# Keyboard.net
KiCad netlist of a schematic drawn in EAGLE
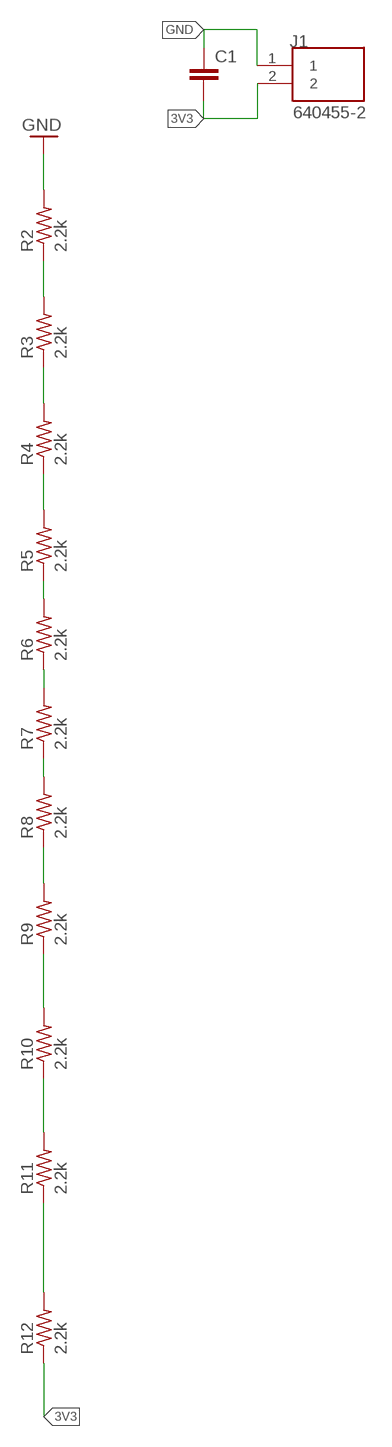
[diagram p0: schematic, sheet 1]

(export (version "E")
  (design (tool "Eeschema 10.0.6"))
  (components
    (comp (ref "C1")
      (value "C-EUC0603")
      (footprint "eagle-import:C0603")
      (libsource (lib "eagle-import") (part "C-EUC0603"))
    )
    (comp (ref "J1")
      (value "640455-2")
      (footprint "eagle-import:TE_640455-2")
      (fields (field (name "MF") "TE Connectivity"))
      (libsource (lib "eagle-import") (part "640455-2"))
    )
    (comp (ref "R2")
      (value "2.2k")
      (footprint "eagle-import:R0603")
      (libsource (lib "eagle-import") (part "R-US_R0603"))
    )
    (comp (ref "R3")
      (value "2.2k")
      (footprint "eagle-import:R0603")
      (libsource (lib "eagle-import") (part "R-US_R0603"))
    )
    (comp (ref "R4")
      (value "2.2k")
      (footprint "eagle-import:R0603")
      (libsource (lib "eagle-import") (part "R-US_R0603"))
    )
    (comp (ref "R5")
      (value "2.2k")
      (footprint "eagle-import:R0603")
      (libsource (lib "eagle-import") (part "R-US_R0603"))
    )
    (comp (ref "R6")
      (value "2.2k")
      (footprint "eagle-import:R0603")
      (libsource (lib "eagle-import") (part "R-US_R0603"))
    )
    (comp (ref "R7")
      (value "2.2k")
      (footprint "eagle-import:R0603")
      (libsource (lib "eagle-import") (part "R-US_R0603"))
    )
    (comp (ref "R8")
      (value "2.2k")
      (footprint "eagle-import:R0603")
      (libsource (lib "eagle-import") (part "R-US_R0603"))
    )
    (comp (ref "R9")
      (value "2.2k")
      (footprint "eagle-import:R0603")
      (libsource (lib "eagle-import") (part "R-US_R0603"))
    )
    (comp (ref "R10")
      (value "2.2k")
      (footprint "eagle-import:R0603")
      (libsource (lib "eagle-import") (part "R-US_R0603"))
    )
    (comp (ref "R11")
      (value "2.2k")
      (footprint "eagle-import:R0603")
      (libsource (lib "eagle-import") (part "R-US_R0603"))
    )
    (comp (ref "R12")
      (value "2.2k")
      (footprint "eagle-import:R0603")
      (libsource (lib "eagle-import") (part "R-US_R0603"))
    )
  )
  (nets
    (net (code "1") (name "3V3") (class "Default")
      (node (ref "C1") (pin "2") (pinfunction "2_2") (pintype "passive"))
      (node (ref "J1") (pin "2") (pinfunction "2_2") (pintype "passive"))
      (node (ref "R12") (pin "1") (pinfunction "1_1") (pintype "passive"))
    )
    (net (code "2") (name "GND") (class "Default")
      (node (ref "C1") (pin "1") (pinfunction "1_1") (pintype "passive"))
      (node (ref "J1") (pin "1") (pinfunction "1_1") (pintype "passive"))
      (node (ref "R2") (pin "2") (pinfunction "2_2") (pintype "passive"))
    )
    (net (code "3") (name "Net-(R2-Pad1)") (class "Default")
      (node (ref "R2") (pin "1") (pinfunction "1_1") (pintype "passive"))
      (node (ref "R3") (pin "2") (pinfunction "2_2") (pintype "passive"))
    )
    (net (code "4") (name "Net-(R3-Pad1)") (class "Default")
      (node (ref "R3") (pin "1") (pinfunction "1_1") (pintype "passive"))
      (node (ref "R4") (pin "2") (pinfunction "2_2") (pintype "passive"))
    )
    (net (code "5") (name "Net-(R4-Pad1)") (class "Default")
      (node (ref "R4") (pin "1") (pinfunction "1_1") (pintype "passive"))
      (node (ref "R5") (pin "2") (pinfunction "2_2") (pintype "passive"))
    )
    (net (code "6") (name "Net-(R5-Pad1)") (class "Default")
      (node (ref "R5") (pin "1") (pinfunction "1_1") (pintype "passive"))
      (node (ref "R6") (pin "2") (pinfunction "2_2") (pintype "passive"))
    )
    (net (code "7") (name "Net-(R6-Pad1)") (class "Default")
      (node (ref "R6") (pin "1") (pinfunction "1_1") (pintype "passive"))
      (node (ref "R7") (pin "2") (pinfunction "2_2") (pintype "passive"))
    )
    (net (code "8") (name "Net-(R7-Pad1)") (class "Default")
      (node (ref "R7") (pin "1") (pinfunction "1_1") (pintype "passive"))
      (node (ref "R8") (pin "2") (pinfunction "2_2") (pintype "passive"))
    )
    (net (code "9") (name "Net-(R8-Pad1)") (class "Default")
      (node (ref "R8") (pin "1") (pinfunction "1_1") (pintype "passive"))
      (node (ref "R9") (pin "2") (pinfunction "2_2") (pintype "passive"))
    )
    (net (code "10") (name "Net-(R10-Pad1)") (class "Default")
      (node (ref "R10") (pin "1") (pinfunction "1_1") (pintype "passive"))
      (node (ref "R11") (pin "2") (pinfunction "2_2") (pintype "passive"))
    )
    (net (code "11") (name "Net-(R10-Pad2)") (class "Default")
      (node (ref "R10") (pin "2") (pinfunction "2_2") (pintype "passive"))
      (node (ref "R9") (pin "1") (pinfunction "1_1") (pintype "passive"))
    )
    (net (code "12") (name "Net-(R11-Pad1)") (class "Default")
      (node (ref "R11") (pin "1") (pinfunction "1_1") (pintype "passive"))
      (node (ref "R12") (pin "2") (pinfunction "2_2") (pintype "passive"))
    )
  )
)
